# L_R_Overcurrent_Analog.net
KiCad netlist of a schematic drawn in EAGLE
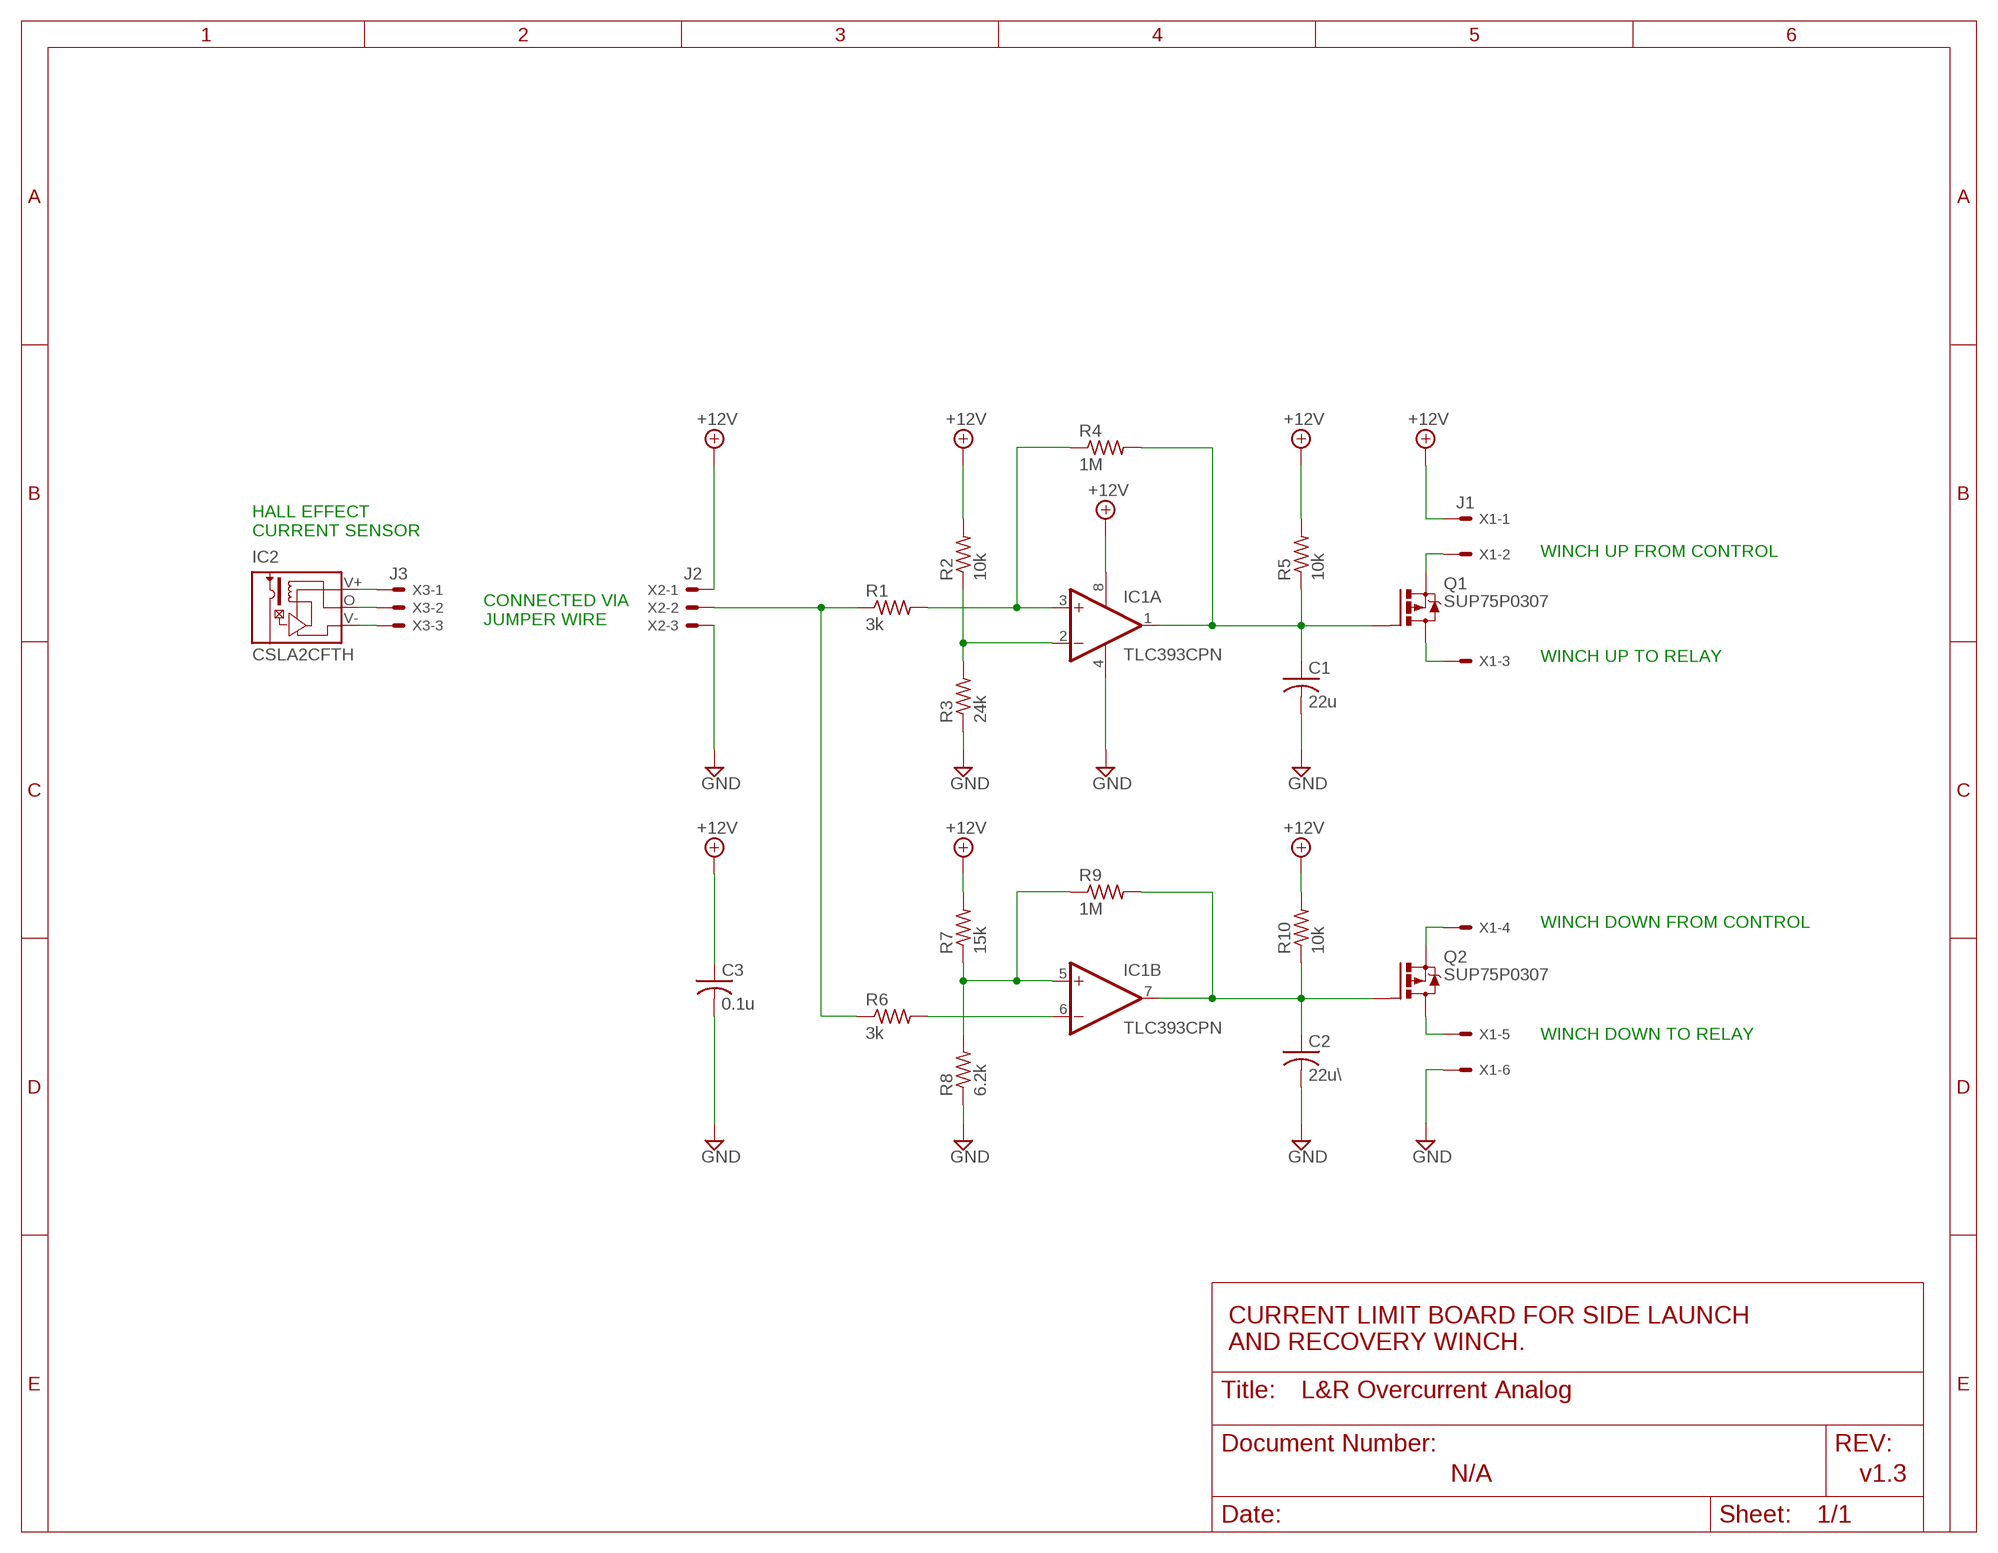
[diagram p0: schematic, sheet 1]

(export (version "E")
  (design (tool "Eeschema 10.0.6"))
  (components
    (comp (ref "C1")
      (value "22u")
      (footprint "eagle-import:C025-050X050")
      (libsource (lib "eagle-import") (part "CAPACITOR-US025-050X050"))
    )
    (comp (ref "C2")
      (value "22u\\")
      (footprint "eagle-import:C025-050X050")
      (libsource (lib "eagle-import") (part "CAPACITOR-US025-050X050"))
    )
    (comp (ref "C3")
      (value "0.1u")
      (footprint "eagle-import:C050-024X044")
      (libsource (lib "eagle-import") (part "CAPACITOR-US"))
    )
    (comp (ref "FRAME1")
      (value "FRAME_A_L")
      (footprint "eagle-import:FRAME_A_L")
      (libsource (lib "eagle-import") (part "FRAME_A_L"))
    )
    (comp (ref "IC1")
      (value "TLC393CPN")
      (footprint "eagle-import:DIL08")
      (libsource (lib "eagle-import") (part "TLC393CPN"))
    )
    (comp (ref "IC2")
      (value "CSLA2CFTH")
      (footprint "eagle-import:CSLA2CF")
      (libsource (lib "eagle-import") (part "CSLA2CFTH"))
    )
    (comp (ref "Q1")
      (value "SUP75P0307")
      (footprint "eagle-import:TO220BV")
      (libsource (lib "eagle-import") (part "SUP75P0307"))
    )
    (comp (ref "Q2")
      (value "SUP75P0307")
      (footprint "eagle-import:TO220BV")
      (libsource (lib "eagle-import") (part "SUP75P0307"))
    )
    (comp (ref "R1")
      (value "3k")
      (footprint "eagle-import:0204_7")
      (libsource (lib "eagle-import") (part "RESISTOR-US0204/7"))
    )
    (comp (ref "R2")
      (value "10k")
      (footprint "eagle-import:0204_7")
      (libsource (lib "eagle-import") (part "RESISTOR-US0204/7"))
    )
    (comp (ref "R3")
      (value "24k")
      (footprint "eagle-import:0204_7")
      (libsource (lib "eagle-import") (part "RESISTOR-US0204/7"))
    )
    (comp (ref "R4")
      (value "1M")
      (footprint "eagle-import:0204_7")
      (libsource (lib "eagle-import") (part "RESISTOR-US0204/7"))
    )
    (comp (ref "R5")
      (value "10k")
      (footprint "eagle-import:0204_7")
      (libsource (lib "eagle-import") (part "RESISTOR-US0204/7"))
    )
    (comp (ref "R6")
      (value "3k")
      (footprint "eagle-import:0204_7")
      (libsource (lib "eagle-import") (part "RESISTOR-US0204/7"))
    )
    (comp (ref "R7")
      (value "15k")
      (footprint "eagle-import:0204_7")
      (libsource (lib "eagle-import") (part "RESISTOR-US0204/7"))
    )
    (comp (ref "R8")
      (value "6.2k")
      (footprint "eagle-import:0204_7")
      (libsource (lib "eagle-import") (part "RESISTOR-US0204/7"))
    )
    (comp (ref "R9")
      (value "1M")
      (footprint "eagle-import:0204_7")
      (libsource (lib "eagle-import") (part "RESISTOR-US0204/7"))
    )
    (comp (ref "R10")
      (value "10k")
      (footprint "eagle-import:0204_7")
      (libsource (lib "eagle-import") (part "RESISTOR-US0204/7"))
    )
    (comp (ref "U$1")
      (value "DOCFIELD")
      (footprint "eagle-import:DOCFIELD")
      (libsource (lib "eagle-import") (part "DOCFIELD"))
    )
    (comp (ref "X1")
      (value "J1")
      (footprint "eagle-import:22-23-2061")
      (fields (field (name "MF") "MOLEX") (field (name "MPN") "22-23-2061"))
      (libsource (lib "eagle-import") (part "6PIN_HEADER"))
    )
    (comp (ref "X2")
      (value "J2")
      (footprint "eagle-import:22-23-2031")
      (fields (field (name "MF") "MOLEX") (field (name "MPN") "22-23-2031"))
      (libsource (lib "eagle-import") (part "22-23-2031"))
    )
    (comp (ref "X3")
      (value "J3")
      (footprint "eagle-import:22-23-2031")
      (fields (field (name "MF") "MOLEX") (field (name "MPN") "22-23-2031"))
      (libsource (lib "eagle-import") (part "22-23-2031"))
    )
  )
  (nets
    (net (code "1") (name "+12V") (class "Default")
      (node (ref "C3") (pin "1") (pinfunction "1_1") (pintype "passive"))
      (node (ref "IC1") (pin "8") (pinfunction "V+_8") (pintype "power_in"))
      (node (ref "R10") (pin "2") (pinfunction "2_2") (pintype "passive"))
      (node (ref "R2") (pin "2") (pinfunction "2_2") (pintype "passive"))
      (node (ref "R5") (pin "2") (pinfunction "2_2") (pintype "passive"))
      (node (ref "R7") (pin "2") (pinfunction "2_2") (pintype "passive"))
      (node (ref "X1") (pin "1") (pinfunction "S_1") (pintype "passive"))
      (node (ref "X2") (pin "1") (pinfunction "S_1") (pintype "passive"))
    )
    (net (code "2") (name "GND") (class "Default")
      (node (ref "C1") (pin "2") (pinfunction "2_2") (pintype "passive"))
      (node (ref "C2") (pin "2") (pinfunction "2_2") (pintype "passive"))
      (node (ref "C3") (pin "2") (pinfunction "2_2") (pintype "passive"))
      (node (ref "IC1") (pin "4") (pinfunction "V-_4") (pintype "power_in"))
      (node (ref "R3") (pin "1") (pinfunction "1_1") (pintype "passive"))
      (node (ref "R8") (pin "1") (pinfunction "1_1") (pintype "passive"))
      (node (ref "X1") (pin "6") (pinfunction "S_6") (pintype "passive"))
      (node (ref "X2") (pin "3") (pinfunction "S_3") (pintype "passive"))
    )
    (net (code "3") (name "Net-(IC1A-+IN)") (class "Default")
      (node (ref "IC1") (pin "3") (pinfunction "+IN_3") (pintype "input"))
      (node (ref "R1") (pin "2") (pinfunction "2_2") (pintype "passive"))
      (node (ref "R4") (pin "1") (pinfunction "1_1") (pintype "passive"))
    )
    (net (code "4") (name "Net-(IC1A--IN)") (class "Default")
      (node (ref "IC1") (pin "2") (pinfunction "-IN_2") (pintype "input"))
      (node (ref "R2") (pin "1") (pinfunction "1_1") (pintype "passive"))
      (node (ref "R3") (pin "2") (pinfunction "2_2") (pintype "passive"))
    )
    (net (code "5") (name "Net-(IC1A-OUT)") (class "Default")
      (node (ref "C1") (pin "1") (pinfunction "1_1") (pintype "passive"))
      (node (ref "IC1") (pin "1") (pinfunction "OUT_1") (pintype "output"))
      (node (ref "Q1") (pin "G") (pinfunction "G_G") (pintype "passive"))
      (node (ref "R4") (pin "2") (pinfunction "2_2") (pintype "passive"))
      (node (ref "R5") (pin "1") (pinfunction "1_1") (pintype "passive"))
    )
    (net (code "6") (name "Net-(IC1B-+IN)") (class "Default")
      (node (ref "IC1") (pin "5") (pinfunction "+IN_5") (pintype "input"))
      (node (ref "R7") (pin "1") (pinfunction "1_1") (pintype "passive"))
      (node (ref "R8") (pin "2") (pinfunction "2_2") (pintype "passive"))
      (node (ref "R9") (pin "1") (pinfunction "1_1") (pintype "passive"))
    )
    (net (code "7") (name "Net-(IC1B--IN)") (class "Default")
      (node (ref "IC1") (pin "6") (pinfunction "-IN_6") (pintype "input"))
      (node (ref "R6") (pin "2") (pinfunction "2_2") (pintype "passive"))
    )
    (net (code "8") (name "Net-(IC1B-OUT)") (class "Default")
      (node (ref "C2") (pin "1") (pinfunction "1_1") (pintype "passive"))
      (node (ref "IC1") (pin "7") (pinfunction "OUT_7") (pintype "output"))
      (node (ref "Q2") (pin "G") (pinfunction "G_G") (pintype "passive"))
      (node (ref "R10") (pin "1") (pinfunction "1_1") (pintype "passive"))
      (node (ref "R9") (pin "2") (pinfunction "2_2") (pintype "passive"))
    )
    (net (code "9") (name "Net-(IC2-M)") (class "Default")
      (node (ref "IC2") (pin "O") (pinfunction "M_O") (pintype "output"))
      (node (ref "X3") (pin "2") (pinfunction "S_2") (pintype "passive"))
    )
    (net (code "10") (name "Net-(X1B-S)") (class "Default")
      (node (ref "Q1") (pin "S") (pinfunction "S_S") (pintype "passive"))
      (node (ref "X1") (pin "2") (pinfunction "S_2") (pintype "passive"))
    )
    (net (code "11") (name "Net-(X1C-S)") (class "Default")
      (node (ref "Q1") (pin "D") (pinfunction "D_D") (pintype "passive"))
      (node (ref "X1") (pin "3") (pinfunction "S_3") (pintype "passive"))
    )
    (net (code "12") (name "Net-(X1D-S)") (class "Default")
      (node (ref "Q2") (pin "S") (pinfunction "S_S") (pintype "passive"))
      (node (ref "X1") (pin "4") (pinfunction "S_4") (pintype "passive"))
    )
    (net (code "13") (name "Net-(X1E-S)") (class "Default")
      (node (ref "Q2") (pin "D") (pinfunction "D_D") (pintype "passive"))
      (node (ref "X1") (pin "5") (pinfunction "S_5") (pintype "passive"))
    )
    (net (code "14") (name "Net-(X2B-S)") (class "Default")
      (node (ref "R1") (pin "1") (pinfunction "1_1") (pintype "passive"))
      (node (ref "R6") (pin "1") (pinfunction "1_1") (pintype "passive"))
      (node (ref "X2") (pin "2") (pinfunction "S_2") (pintype "passive"))
    )
    (net (code "15") (name "Net-(X3A-S)") (class "Default")
      (node (ref "IC2") (pin "V+") (pinfunction "V+_V+") (pintype "input"))
      (node (ref "X3") (pin "1") (pinfunction "S_1") (pintype "passive"))
    )
    (net (code "16") (name "Net-(X3C-S)") (class "Default")
      (node (ref "IC2") (pin "V-") (pinfunction "V-_V-") (pintype "input"))
      (node (ref "X3") (pin "3") (pinfunction "S_3") (pintype "passive"))
    )
  )
)
